# ESP32P4.net
KiCad netlist of a schematic drawn in Altium Designer
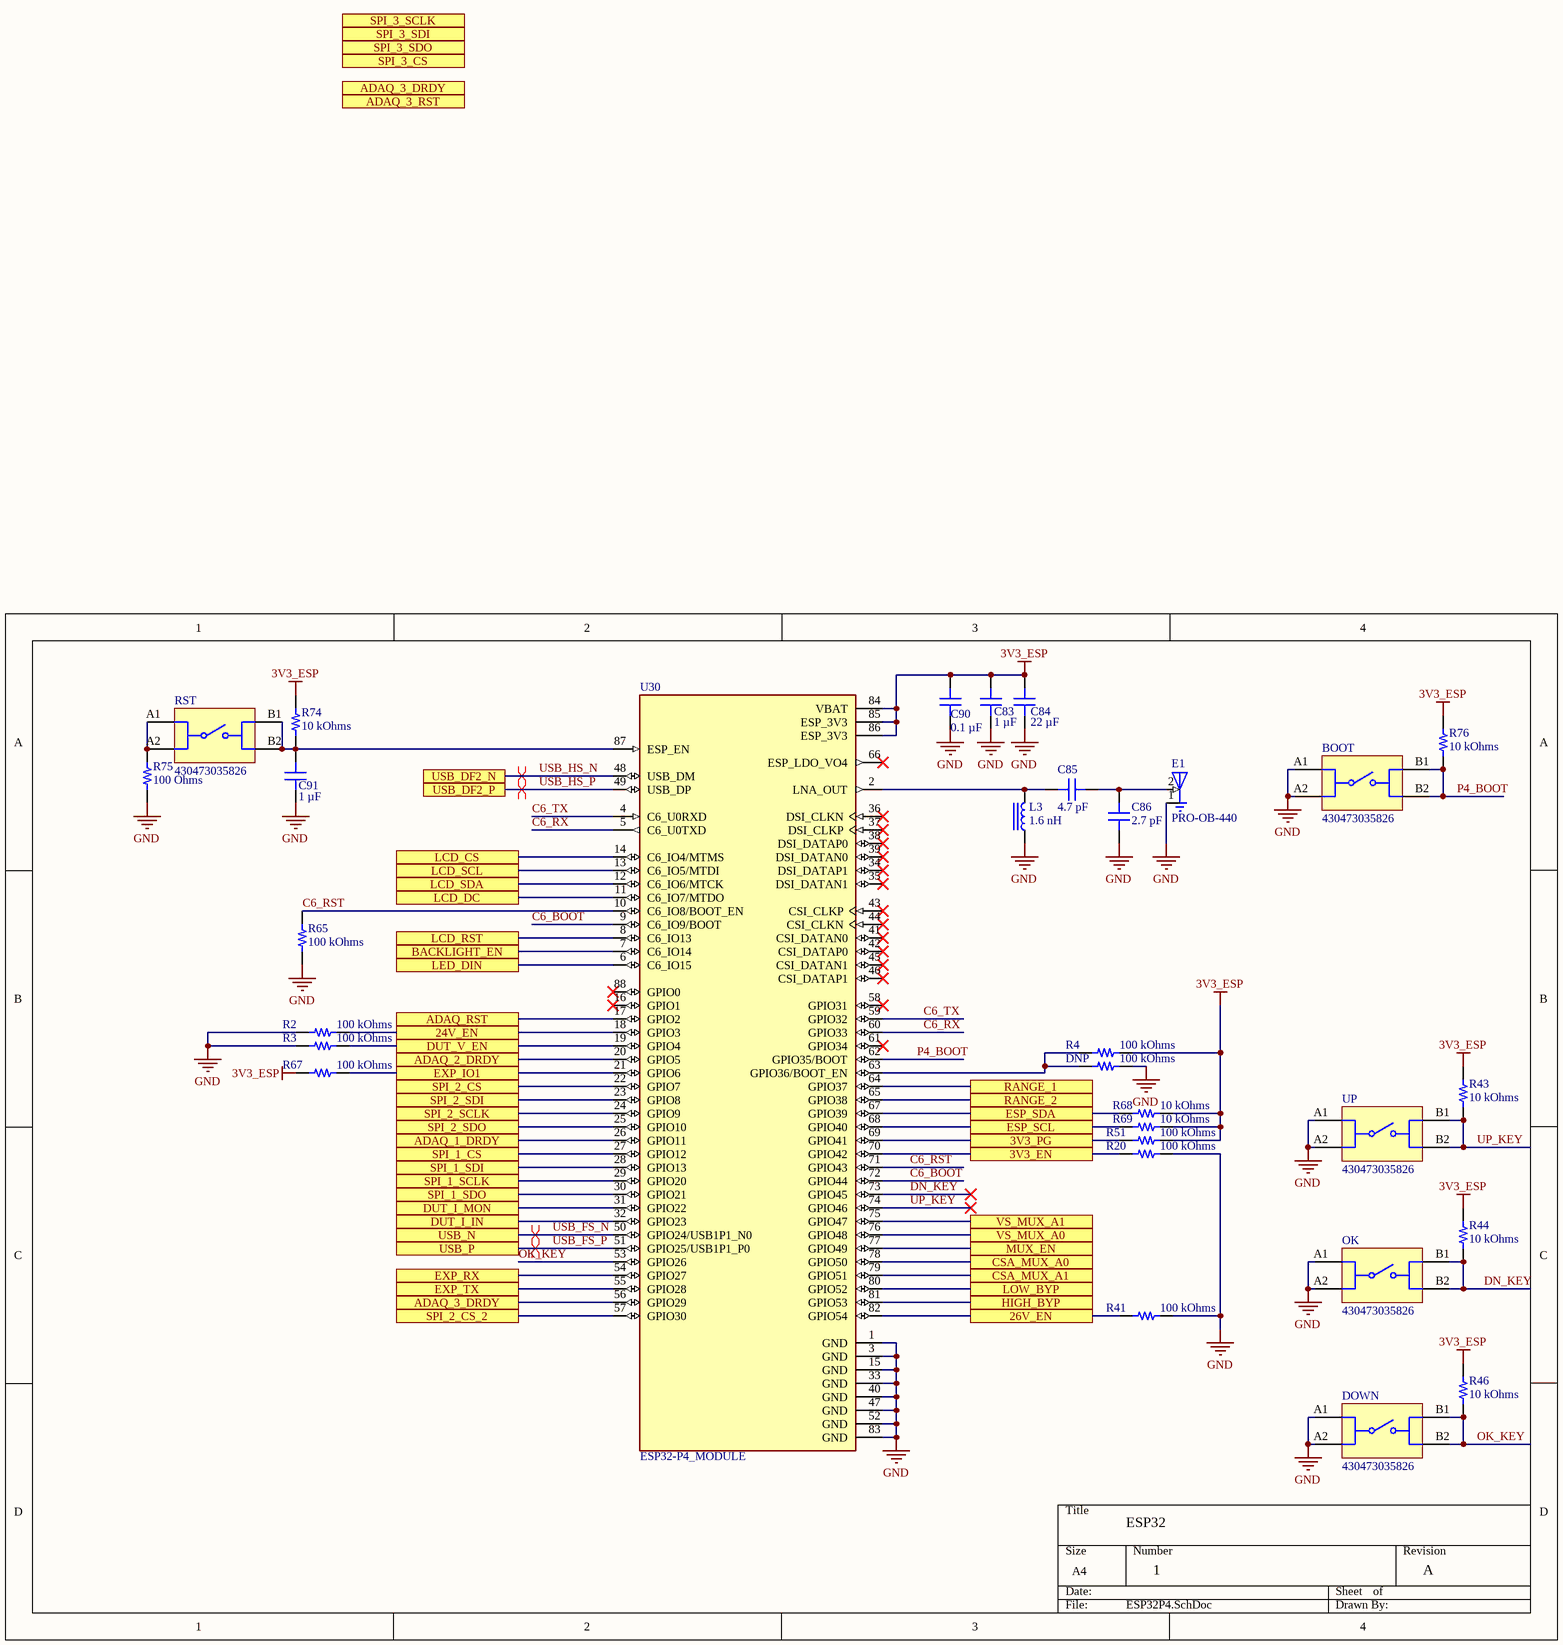
[diagram p0: ESP32P4.SchDoc]

(export (version "E")
  (design (tool "Eeschema 10.0.6"))
  (components
    (comp (ref "BOOT")
      (value "430473035826")
      (footprint "430473035826")
      (description "Switch Tactile Spst-no 0.05A 12V")
      (libsource (lib "Altium Content Vault") (part "SPST-NO_4P"))
    )
    (comp (ref "C83")
      (value "1 µF")
      (footprint "CAP 0603_1608")
      (description "SMT Capacitor")
      (fields
        (field (name "PART NUMBER") "GMC10X7R105M50NT")
        (field (name "MANUFACTURER") "Cal-Chip Electronics, Inc.")
      )
      (libsource (lib "Altium DB") (part "Capacitor"))
    )
    (comp (ref "C84")
      (value "22 µF")
      (footprint "CAP 0603_1608")
      (description "SMT Capacitor")
      (fields
        (field (name "PART NUMBER") "GRM188C61C226ME01D")
        (field (name "MANUFACTURER") "Murata Electronics")
      )
      (libsource (lib "Altium DB") (part "Capacitor"))
    )
    (comp (ref "C85")
      (value "4.7 pF")
      (footprint "CAP 0603_1608")
      (description "SMT Capacitor")
      (fields (field (name "PART NUMBER") "06035C4R7KAT2A") (field (name "MANUFACTURER") "KYOCERA AVX"))
      (libsource (lib "Altium DB") (part "Capacitor"))
    )
    (comp (ref "C86")
      (value "2.7 pF")
      (footprint "CAP 0603_1608")
      (description "SMT Capacitor")
      (fields (field (name "PART NUMBER") "C0603C279D5GAC7867") (field (name "MANUFACTURER") "KEMET"))
      (libsource (lib "Altium DB") (part "Capacitor"))
    )
    (comp (ref "C90")
      (value "0.1 µF")
      (footprint "CAP 0603_1608")
      (description "SMT Capacitor")
      (fields (field (name "PART NUMBER") "C0603C104M5RACTU") (field (name "MANUFACTURER") "KEMET"))
      (libsource (lib "Altium DB") (part "Capacitor"))
    )
    (comp (ref "C91")
      (value "1 µF")
      (footprint "CAP 0603_1608")
      (description "SMT Capacitor")
      (fields
        (field (name "PART NUMBER") "GMC10X7R105M50NT")
        (field (name "MANUFACTURER") "Cal-Chip Electronics, Inc.")
      )
      (libsource (lib "Altium DB") (part "Capacitor"))
    )
    (comp (ref "DNP")
      (value "100 kOhms")
      (footprint "RES 0603_1608")
      (description "RES SMD 100K OHM 1% 1/3W 0603")
      (fields
        (field (name "MANUFACTURER") "Panasonic Electronic Components")
        (field (name "PART NUMBER") "ERJ-PA3F1003V")
      )
      (libsource (lib "Altium DB") (part "Resistor"))
    )
    (comp (ref "DOWN")
      (value "430473035826")
      (footprint "430473035826")
      (description "Switch Tactile Spst-no 0.05A 12V")
      (libsource (lib "Altium Content Vault") (part "SPST-NO_4P"))
    )
    (comp (ref "E1")
      (value "PRO-OB-440")
      (footprint "XDCR_PRO-OB-440")
      (fields (field (name "MF") "Abracon"))
      (libsource (lib "Lib") (part "PRO-OB-440"))
    )
    (comp (ref "L3")
      (value "1.6 nH")
      (footprint "Murata LQW18 0603")
      (description "FIXED IND 1.6NH 700MA 30MOHM SMD")
      (fields
        (field (name "PART NUMBER") "LQW18AS1N6J0ZD")
        (field (name "MANUFACTURER") "Murata Electronics")
      )
      (libsource (lib "Altium DB") (part "Inductor"))
    )
    (comp (ref "OK")
      (value "430473035826")
      (footprint "430473035826")
      (description "Switch Tactile Spst-no 0.05A 12V")
      (libsource (lib "Altium Content Vault") (part "SPST-NO_4P"))
    )
    (comp (ref "R2")
      (value "100 kOhms")
      (footprint "RES 0603_1608")
      (description "RES SMD 100K OHM 1% 1/3W 0603")
      (fields
        (field (name "MANUFACTURER") "Panasonic Electronic Components")
        (field (name "PART NUMBER") "ERJ-PA3F1003V")
      )
      (libsource (lib "Altium DB") (part "Resistor"))
    )
    (comp (ref "R3")
      (value "100 kOhms")
      (footprint "RES 0603_1608")
      (description "RES SMD 100K OHM 1% 1/3W 0603")
      (fields
        (field (name "MANUFACTURER") "Panasonic Electronic Components")
        (field (name "PART NUMBER") "ERJ-PA3F1003V")
      )
      (libsource (lib "Altium DB") (part "Resistor"))
    )
    (comp (ref "R4")
      (value "100 kOhms")
      (footprint "RES 0603_1608")
      (description "RES SMD 100K OHM 1% 1/3W 0603")
      (fields
        (field (name "MANUFACTURER") "Panasonic Electronic Components")
        (field (name "PART NUMBER") "ERJ-PA3F1003V")
      )
      (libsource (lib "Altium DB") (part "Resistor"))
    )
    (comp (ref "R20")
      (value "100 kOhms")
      (footprint "RES 0603_1608")
      (description "RES SMD 100K OHM 1% 1/3W 0603")
      (fields
        (field (name "MANUFACTURER") "Panasonic Electronic Components")
        (field (name "PART NUMBER") "ERJ-PA3F1003V")
      )
      (libsource (lib "Altium DB") (part "Resistor"))
    )
    (comp (ref "R41")
      (value "100 kOhms")
      (footprint "RES 0603_1608")
      (description "RES SMD 100K OHM 1% 1/3W 0603")
      (fields
        (field (name "MANUFACTURER") "Panasonic Electronic Components")
        (field (name "PART NUMBER") "ERJ-PA3F1003V")
      )
      (libsource (lib "Altium DB") (part "Resistor"))
    )
    (comp (ref "R43")
      (value "10 kOhms")
      (footprint "RES 0603_1608")
      (description "RES SMD 10K OHM 1% 1/3W 0603")
      (fields
        (field (name "MANUFACTURER") "Panasonic Electronic Components")
        (field (name "PART NUMBER") "ERJ-PA3F1002V")
      )
      (libsource (lib "Altium DB") (part "Resistor"))
    )
    (comp (ref "R44")
      (value "10 kOhms")
      (footprint "RES 0603_1608")
      (description "RES SMD 10K OHM 1% 1/3W 0603")
      (fields
        (field (name "MANUFACTURER") "Panasonic Electronic Components")
        (field (name "PART NUMBER") "ERJ-PA3F1002V")
      )
      (libsource (lib "Altium DB") (part "Resistor"))
    )
    (comp (ref "R46")
      (value "10 kOhms")
      (footprint "RES 0603_1608")
      (description "RES SMD 10K OHM 1% 1/3W 0603")
      (fields
        (field (name "MANUFACTURER") "Panasonic Electronic Components")
        (field (name "PART NUMBER") "ERJ-PA3F1002V")
      )
      (libsource (lib "Altium DB") (part "Resistor"))
    )
    (comp (ref "R51")
      (value "100 kOhms")
      (footprint "RES 0603_1608")
      (description "RES SMD 100K OHM 1% 1/3W 0603")
      (fields
        (field (name "MANUFACTURER") "Panasonic Electronic Components")
        (field (name "PART NUMBER") "ERJ-PA3F1003V")
      )
      (libsource (lib "Altium DB") (part "Resistor"))
    )
    (comp (ref "R65")
      (value "100 kOhms")
      (footprint "RES 0603_1608")
      (description "RES SMD 100K OHM 1% 1/3W 0603")
      (fields
        (field (name "MANUFACTURER") "Panasonic Electronic Components")
        (field (name "PART NUMBER") "ERJ-PA3F1003V")
      )
      (libsource (lib "Altium DB") (part "Resistor"))
    )
    (comp (ref "R67")
      (value "100 kOhms")
      (footprint "RES 0603_1608")
      (description "RES SMD 100K OHM 1% 1/3W 0603")
      (fields
        (field (name "MANUFACTURER") "Panasonic Electronic Components")
        (field (name "PART NUMBER") "ERJ-PA3F1003V")
      )
      (libsource (lib "Altium DB") (part "Resistor"))
    )
    (comp (ref "R68")
      (value "10 kOhms")
      (footprint "RES 0603_1608")
      (description "RES SMD 10K OHM 1% 1/3W 0603")
      (fields
        (field (name "MANUFACTURER") "Panasonic Electronic Components")
        (field (name "PART NUMBER") "ERJ-PA3F1002V")
      )
      (libsource (lib "Altium DB") (part "Resistor"))
    )
    (comp (ref "R69")
      (value "10 kOhms")
      (footprint "RES 0603_1608")
      (description "RES SMD 10K OHM 1% 1/3W 0603")
      (fields
        (field (name "MANUFACTURER") "Panasonic Electronic Components")
        (field (name "PART NUMBER") "ERJ-PA3F1002V")
      )
      (libsource (lib "Altium DB") (part "Resistor"))
    )
    (comp (ref "R74")
      (value "10 kOhms")
      (footprint "RES 0603_1608")
      (description "RES SMD 10K OHM 1% 1/3W 0603")
      (fields
        (field (name "MANUFACTURER") "Panasonic Electronic Components")
        (field (name "PART NUMBER") "ERJ-PA3F1002V")
      )
      (libsource (lib "Altium DB") (part "Resistor"))
    )
    (comp (ref "R75")
      (value "100 Ohms")
      (footprint "RES 0603_1608")
      (description "RES SMD 100 OHM 1% 1/3W 0603")
      (fields
        (field (name "MANUFACTURER") "Panasonic Electronic Components")
        (field (name "PART NUMBER") "ERJ-PA3F1000V")
      )
      (libsource (lib "") (part "Resistor_1"))
    )
    (comp (ref "R76")
      (value "10 kOhms")
      (footprint "RES 0603_1608")
      (description "RES SMD 10K OHM 1% 1/3W 0603")
      (fields
        (field (name "MANUFACTURER") "Panasonic Electronic Components")
        (field (name "PART NUMBER") "ERJ-PA3F1002V")
      )
      (libsource (lib "Altium DB") (part "Resistor"))
    )
    (comp (ref "RST")
      (value "430473035826")
      (footprint "430473035826")
      (description "Switch Tactile Spst-no 0.05A 12V")
      (libsource (lib "Altium Content Vault") (part "SPST-NO_4P"))
    )
    (comp (ref "U30")
      (value "ESP32-P4_MODULE")
      (footprint "XCVR_ESP32-P4_MODULE")
      (description "Dual-core RISC-V high-performance module")
      (fields (field (name "MF") "Waveshare Electronics") (field (name "MP") "ESP32-P4 Module"))
      (libsource (lib "Lib") (part "ESP32-P4_MODULE"))
    )
    (comp (ref "UP")
      (value "430473035826")
      (footprint "430473035826")
      (description "Switch Tactile Spst-no 0.05A 12V")
      (libsource (lib "Altium Content Vault") (part "SPST-NO_4P"))
    )
  )
  (nets
    (net (code "1") (name "/3V3_EN") (class "Default")
      (node (ref "R20") (pin "1") (pinfunction "1_1") (pintype "passive"))
      (node (ref "U30") (pin "70") (pinfunction "GPIO42_70") (pintype "bidirectional"))
    )
    (net (code "2") (name "/3V3_PG") (class "Default")
      (node (ref "R51") (pin "1") (pinfunction "1_1") (pintype "passive"))
      (node (ref "U30") (pin "69") (pinfunction "GPIO41_69") (pintype "bidirectional"))
    )
    (net (code "3") (name "/24V_EN") (class "Default")
      (node (ref "R2") (pin "2") (pinfunction "2_2") (pintype "passive"))
      (node (ref "U30") (pin "18") (pinfunction "GPIO3_18") (pintype "bidirectional"))
    )
    (net (code "4") (name "/26V_EN") (class "Default")
      (node (ref "R41") (pin "1") (pinfunction "1_1") (pintype "passive"))
      (node (ref "U30") (pin "82") (pinfunction "GPIO54_82") (pintype "bidirectional"))
    )
    (net (code "5") (name "/ADAQ_1_DRDY") (class "Default")
      (node (ref "U30") (pin "26") (pinfunction "GPIO11_26") (pintype "bidirectional"))
    )
    (net (code "6") (name "/ADAQ_2_DRDY") (class "Default")
      (node (ref "U30") (pin "20") (pinfunction "GPIO5_20") (pintype "bidirectional"))
    )
    (net (code "7") (name "/ADAQ_3_DRDY") (class "Default")
      (node (ref "U30") (pin "56") (pinfunction "GPIO29_56") (pintype "bidirectional"))
    )
    (net (code "9") (name "/ADAQ_RST") (class "Default")
      (node (ref "U30") (pin "17") (pinfunction "GPIO2_17") (pintype "bidirectional"))
    )
    (net (code "10") (name "/BACKLIGHT_EN") (class "Default")
      (node (ref "U30") (pin "7") (pinfunction "C6_IO14_7") (pintype "bidirectional"))
    )
    (net (code "11") (name "/C6_BOOT") (class "Default")
      (node (ref "U30") (pin "72") (pinfunction "GPIO44_72") (pintype "bidirectional"))
      (node (ref "U30") (pin "9") (pinfunction "C6_IO9/BOOT_9") (pintype "bidirectional"))
    )
    (net (code "12") (name "/C6_RST") (class "Default")
      (node (ref "R65") (pin "1") (pinfunction "1_1") (pintype "passive"))
      (node (ref "U30") (pin "10") (pinfunction "C6_IO8/BOOT_EN_10") (pintype "bidirectional"))
      (node (ref "U30") (pin "71") (pinfunction "GPIO43_71") (pintype "bidirectional"))
    )
    (net (code "13") (name "/C6_RX") (class "Default")
      (node (ref "U30") (pin "5") (pinfunction "C6_U0TXD_5") (pintype "output"))
      (node (ref "U30") (pin "60") (pinfunction "GPIO33_60") (pintype "bidirectional"))
    )
    (net (code "14") (name "/C6_TX") (class "Default")
      (node (ref "U30") (pin "4") (pinfunction "C6_U0RXD_4") (pintype "input"))
      (node (ref "U30") (pin "59") (pinfunction "GPIO32_59") (pintype "bidirectional"))
    )
    (net (code "15") (name "/CSA_MUX_A0") (class "Default")
      (node (ref "U30") (pin "78") (pinfunction "GPIO50_78") (pintype "bidirectional"))
    )
    (net (code "16") (name "/CSA_MUX_A1") (class "Default")
      (node (ref "U30") (pin "79") (pinfunction "GPIO51_79") (pintype "bidirectional"))
    )
    (net (code "17") (name "/DN_KEY") (class "Default")
      (node (ref "OK") (pin "B1") (pinfunction "B1_B1") (pintype "passive"))
      (node (ref "OK") (pin "B2") (pinfunction "B2_B2") (pintype "passive"))
      (node (ref "R44") (pin "1") (pinfunction "1_1") (pintype "passive"))
      (node (ref "U30") (pin "73") (pinfunction "GPIO45_73") (pintype "bidirectional"))
    )
    (net (code "18") (name "/DUT_I_IN") (class "Default")
      (node (ref "U30") (pin "32") (pinfunction "GPIO23_32") (pintype "bidirectional"))
    )
    (net (code "19") (name "/DUT_I_MON") (class "Default")
      (node (ref "U30") (pin "31") (pinfunction "GPIO22_31") (pintype "bidirectional"))
    )
    (net (code "20") (name "/DUT_V_EN") (class "Default")
      (node (ref "R3") (pin "2") (pinfunction "2_2") (pintype "passive"))
      (node (ref "U30") (pin "19") (pinfunction "GPIO4_19") (pintype "bidirectional"))
    )
    (net (code "21") (name "/ESP_SCL") (class "Default")
      (node (ref "R69") (pin "1") (pinfunction "1_1") (pintype "passive"))
      (node (ref "U30") (pin "68") (pinfunction "GPIO40_68") (pintype "bidirectional"))
    )
    (net (code "22") (name "/ESP_SDA") (class "Default")
      (node (ref "R68") (pin "1") (pinfunction "1_1") (pintype "passive"))
      (node (ref "U30") (pin "67") (pinfunction "GPIO39_67") (pintype "bidirectional"))
    )
    (net (code "23") (name "/EXP_IO1") (class "Default")
      (node (ref "R67") (pin "2") (pinfunction "2_2") (pintype "passive"))
      (node (ref "U30") (pin "21") (pinfunction "GPIO6_21") (pintype "bidirectional"))
    )
    (net (code "24") (name "/EXP_RX") (class "Default")
      (node (ref "U30") (pin "54") (pinfunction "GPIO27_54") (pintype "bidirectional"))
    )
    (net (code "25") (name "/EXP_TX") (class "Default")
      (node (ref "U30") (pin "55") (pinfunction "GPIO28_55") (pintype "bidirectional"))
    )
    (net (code "26") (name "/HIGH_BYP") (class "Default")
      (node (ref "U30") (pin "81") (pinfunction "GPIO53_81") (pintype "bidirectional"))
    )
    (net (code "27") (name "/LCD_CS") (class "Default")
      (node (ref "U30") (pin "14") (pinfunction "C6_IO4/MTMS_14") (pintype "bidirectional"))
    )
    (net (code "28") (name "/LCD_DC") (class "Default")
      (node (ref "U30") (pin "11") (pinfunction "C6_IO7/MTDO_11") (pintype "bidirectional"))
    )
    (net (code "29") (name "/LCD_RST") (class "Default")
      (node (ref "U30") (pin "8") (pinfunction "C6_IO13_8") (pintype "bidirectional"))
    )
    (net (code "30") (name "/LCD_SCL") (class "Default")
      (node (ref "U30") (pin "13") (pinfunction "C6_IO5/MTDI_13") (pintype "bidirectional"))
    )
    (net (code "31") (name "/LCD_SDA") (class "Default")
      (node (ref "U30") (pin "12") (pinfunction "C6_IO6/MTCK_12") (pintype "bidirectional"))
    )
    (net (code "32") (name "/LED_DIN") (class "Default")
      (node (ref "U30") (pin "6") (pinfunction "C6_IO15_6") (pintype "bidirectional"))
    )
    (net (code "33") (name "/LOW_BYP") (class "Default")
      (node (ref "U30") (pin "80") (pinfunction "GPIO52_80") (pintype "bidirectional"))
    )
    (net (code "34") (name "/MUX_EN") (class "Default")
      (node (ref "U30") (pin "77") (pinfunction "GPIO49_77") (pintype "bidirectional"))
    )
    (net (code "35") (name "/OK_KEY") (class "Default")
      (node (ref "DOWN") (pin "B1") (pinfunction "B1_B1") (pintype "passive"))
      (node (ref "DOWN") (pin "B2") (pinfunction "B2_B2") (pintype "passive"))
      (node (ref "R46") (pin "1") (pinfunction "1_1") (pintype "passive"))
      (node (ref "U30") (pin "53") (pinfunction "GPIO26_53") (pintype "bidirectional"))
    )
    (net (code "36") (name "/P4_BOOT") (class "Default")
      (node (ref "BOOT") (pin "B1") (pinfunction "B1_B1") (pintype "passive"))
      (node (ref "BOOT") (pin "B2") (pinfunction "B2_B2") (pintype "passive"))
      (node (ref "R76") (pin "1") (pinfunction "1_1") (pintype "passive"))
      (node (ref "U30") (pin "62") (pinfunction "GPIO35/BOOT_62") (pintype "bidirectional"))
    )
    (net (code "37") (name "/RANGE_1") (class "Default")
      (node (ref "U30") (pin "64") (pinfunction "GPIO37_64") (pintype "bidirectional"))
    )
    (net (code "38") (name "/RANGE_2") (class "Default")
      (node (ref "U30") (pin "65") (pinfunction "GPIO38_65") (pintype "bidirectional"))
    )
    (net (code "39") (name "/SPI_1_CS") (class "Default")
      (node (ref "U30") (pin "27") (pinfunction "GPIO12_27") (pintype "bidirectional"))
    )
    (net (code "40") (name "/SPI_1_SCLK") (class "Default")
      (node (ref "U30") (pin "29") (pinfunction "GPIO20_29") (pintype "bidirectional"))
    )
    (net (code "41") (name "/SPI_1_SDI") (class "Default")
      (node (ref "U30") (pin "28") (pinfunction "GPIO13_28") (pintype "bidirectional"))
    )
    (net (code "42") (name "/SPI_1_SDO") (class "Default")
      (node (ref "U30") (pin "30") (pinfunction "GPIO21_30") (pintype "bidirectional"))
    )
    (net (code "43") (name "/SPI_2_CS") (class "Default")
      (node (ref "U30") (pin "22") (pinfunction "GPIO7_22") (pintype "bidirectional"))
    )
    (net (code "44") (name "/SPI_2_CS_2") (class "Default")
      (node (ref "U30") (pin "57") (pinfunction "GPIO30_57") (pintype "bidirectional"))
    )
    (net (code "45") (name "/SPI_2_SCLK") (class "Default")
      (node (ref "U30") (pin "24") (pinfunction "GPIO9_24") (pintype "bidirectional"))
    )
    (net (code "46") (name "/SPI_2_SDI") (class "Default")
      (node (ref "U30") (pin "23") (pinfunction "GPIO8_23") (pintype "bidirectional"))
    )
    (net (code "47") (name "/SPI_2_SDO") (class "Default")
      (node (ref "U30") (pin "25") (pinfunction "GPIO10_25") (pintype "bidirectional"))
    )
    (net (code "52") (name "/UP_KEY") (class "Default")
      (node (ref "R43") (pin "1") (pinfunction "1_1") (pintype "passive"))
      (node (ref "U30") (pin "74") (pinfunction "GPIO46_74") (pintype "bidirectional"))
      (node (ref "UP") (pin "B1") (pinfunction "B1_B1") (pintype "passive"))
      (node (ref "UP") (pin "B2") (pinfunction "B2_B2") (pintype "passive"))
    )
    (net (code "53") (name "/USB_FS_N") (class "Default")
      (node (ref "U30") (pin "50") (pinfunction "GPIO24/USB1P1_N0_50") (pintype "bidirectional"))
    )
    (net (code "54") (name "/USB_FS_P") (class "Default")
      (node (ref "U30") (pin "51") (pinfunction "GPIO25/USB1P1_P0_51") (pintype "bidirectional"))
    )
    (net (code "55") (name "/USB_HS_N") (class "Default")
      (node (ref "U30") (pin "48") (pinfunction "USB_DM_48") (pintype "bidirectional"))
    )
    (net (code "56") (name "/USB_HS_P") (class "Default")
      (node (ref "U30") (pin "49") (pinfunction "USB_DP_49") (pintype "bidirectional"))
    )
    (net (code "57") (name "/VS_MUX_A0") (class "Default")
      (node (ref "U30") (pin "76") (pinfunction "GPIO48_76") (pintype "bidirectional"))
    )
    (net (code "58") (name "/VS_MUX_A1") (class "Default")
      (node (ref "U30") (pin "75") (pinfunction "GPIO47_75") (pintype "bidirectional"))
    )
    (net (code "59") (name "3V3_ESP") (class "Default")
      (node (ref "C83") (pin "2") (pinfunction "2_2") (pintype "passive"))
      (node (ref "C84") (pin "2") (pinfunction "2_2") (pintype "passive"))
      (node (ref "C90") (pin "2") (pinfunction "2_2") (pintype "passive"))
      (node (ref "R4") (pin "2") (pinfunction "2_2") (pintype "passive"))
      (node (ref "R43") (pin "2") (pinfunction "2_2") (pintype "passive"))
      (node (ref "R44") (pin "2") (pinfunction "2_2") (pintype "passive"))
      (node (ref "R46") (pin "2") (pinfunction "2_2") (pintype "passive"))
      (node (ref "R51") (pin "2") (pinfunction "2_2") (pintype "passive"))
      (node (ref "R67") (pin "1") (pinfunction "1_1") (pintype "passive"))
      (node (ref "R68") (pin "2") (pinfunction "2_2") (pintype "passive"))
      (node (ref "R69") (pin "2") (pinfunction "2_2") (pintype "passive"))
      (node (ref "R74") (pin "2") (pinfunction "2_2") (pintype "passive"))
      (node (ref "R76") (pin "2") (pinfunction "2_2") (pintype "passive"))
      (node (ref "U30") (pin "84") (pinfunction "VBAT_84") (pintype "power_in"))
      (node (ref "U30") (pin "85") (pinfunction "ESP_3V3_85") (pintype "power_in"))
      (node (ref "U30") (pin "86") (pinfunction "ESP_3V3_86") (pintype "power_in"))
    )
    (net (code "60") (name "GND") (class "Default")
      (node (ref "BOOT") (pin "A1") (pinfunction "A1_A1") (pintype "passive"))
      (node (ref "BOOT") (pin "A2") (pinfunction "A2_A2") (pintype "passive"))
      (node (ref "C83") (pin "1") (pinfunction "1_1") (pintype "passive"))
      (node (ref "C84") (pin "1") (pinfunction "1_1") (pintype "passive"))
      (node (ref "C86") (pin "1") (pinfunction "1_1") (pintype "passive"))
      (node (ref "C90") (pin "1") (pinfunction "1_1") (pintype "passive"))
      (node (ref "C91") (pin "1") (pinfunction "1_1") (pintype "passive"))
      (node (ref "DNP") (pin "2") (pinfunction "2_2") (pintype "passive"))
      (node (ref "DOWN") (pin "A1") (pinfunction "A1_A1") (pintype "passive"))
      (node (ref "DOWN") (pin "A2") (pinfunction "A2_A2") (pintype "passive"))
      (node (ref "E1") (pin "1") (pinfunction "GND_1") (pintype "power_in"))
      (node (ref "L3") (pin "1") (pinfunction "1_1") (pintype "passive"))
      (node (ref "OK") (pin "A1") (pinfunction "A1_A1") (pintype "passive"))
      (node (ref "OK") (pin "A2") (pinfunction "A2_A2") (pintype "passive"))
      (node (ref "R2") (pin "1") (pinfunction "1_1") (pintype "passive"))
      (node (ref "R20") (pin "2") (pinfunction "2_2") (pintype "passive"))
      (node (ref "R3") (pin "1") (pinfunction "1_1") (pintype "passive"))
      (node (ref "R41") (pin "2") (pinfunction "2_2") (pintype "passive"))
      (node (ref "R65") (pin "2") (pinfunction "2_2") (pintype "passive"))
      (node (ref "R75") (pin "1") (pinfunction "1_1") (pintype "passive"))
      (node (ref "U30") (pin "1") (pinfunction "GND_1") (pintype "power_in"))
      (node (ref "U30") (pin "15") (pinfunction "GND_15") (pintype "power_in"))
      (node (ref "U30") (pin "3") (pinfunction "GND_3") (pintype "power_in"))
      (node (ref "U30") (pin "33") (pinfunction "GND_33") (pintype "power_in"))
      (node (ref "U30") (pin "40") (pinfunction "GND_40") (pintype "power_in"))
      (node (ref "U30") (pin "47") (pinfunction "GND_47") (pintype "power_in"))
      (node (ref "U30") (pin "52") (pinfunction "GND_52") (pintype "power_in"))
      (node (ref "U30") (pin "83") (pinfunction "GND_83") (pintype "power_in"))
      (node (ref "UP") (pin "A1") (pinfunction "A1_A1") (pintype "passive"))
      (node (ref "UP") (pin "A2") (pinfunction "A2_A2") (pintype "passive"))
    )
    (net (code "61") (name "Net-(E1-FEED)") (class "Default")
      (node (ref "C85") (pin "1") (pinfunction "1_1") (pintype "passive"))
      (node (ref "C86") (pin "2") (pinfunction "2_2") (pintype "passive"))
      (node (ref "E1") (pin "2") (pinfunction "FEED_2") (pintype "input"))
    )
    (net (code "62") (name "Net-(R75-Pad2)") (class "Default")
      (node (ref "R75") (pin "2") (pinfunction "2_2") (pintype "passive"))
      (node (ref "RST") (pin "A1") (pinfunction "A1_A1") (pintype "passive"))
      (node (ref "RST") (pin "A2") (pinfunction "A2_A2") (pintype "passive"))
    )
    (net (code "63") (name "Net-(U30-ESP_EN)") (class "Default")
      (node (ref "C91") (pin "2") (pinfunction "2_2") (pintype "passive"))
      (node (ref "R74") (pin "1") (pinfunction "1_1") (pintype "passive"))
      (node (ref "RST") (pin "B1") (pinfunction "B1_B1") (pintype "passive"))
      (node (ref "RST") (pin "B2") (pinfunction "B2_B2") (pintype "passive"))
      (node (ref "U30") (pin "87") (pinfunction "ESP_EN_87") (pintype "input"))
    )
    (net (code "64") (name "Net-(U30-GPIO36{slash}BOOT_EN)") (class "Default")
      (node (ref "DNP") (pin "1") (pinfunction "1_1") (pintype "passive"))
      (node (ref "R4") (pin "1") (pinfunction "1_1") (pintype "passive"))
      (node (ref "U30") (pin "63") (pinfunction "GPIO36/BOOT_EN_63") (pintype "bidirectional"))
    )
    (net (code "65") (name "Net-(U30-LNA_OUT)") (class "Default")
      (node (ref "C85") (pin "2") (pinfunction "2_2") (pintype "passive"))
      (node (ref "L3") (pin "2") (pinfunction "2_2") (pintype "passive"))
      (node (ref "U30") (pin "2") (pinfunction "LNA_OUT_2") (pintype "output"))
    )
    (net (code "66") (name "unconnected-(U30-CSI_CLKN-Pad44)") (class "Default")
      (node (ref "U30") (pin "44") (pinfunction "CSI_CLKN_44") (pintype "input+no_connect"))
    )
    (net (code "67") (name "unconnected-(U30-CSI_CLKP-Pad43)") (class "Default")
      (node (ref "U30") (pin "43") (pinfunction "CSI_CLKP_43") (pintype "input+no_connect"))
    )
    (net (code "68") (name "unconnected-(U30-CSI_DATAN0-Pad41)") (class "Default")
      (node (ref "U30") (pin "41") (pinfunction "CSI_DATAN0_41") (pintype "bidirectional+no_connect"))
    )
    (net (code "69") (name "unconnected-(U30-CSI_DATAN1-Pad45)") (class "Default")
      (node (ref "U30") (pin "45") (pinfunction "CSI_DATAN1_45") (pintype "bidirectional+no_connect"))
    )
    (net (code "70") (name "unconnected-(U30-CSI_DATAP0-Pad42)") (class "Default")
      (node (ref "U30") (pin "42") (pinfunction "CSI_DATAP0_42") (pintype "bidirectional+no_connect"))
    )
    (net (code "71") (name "unconnected-(U30-CSI_DATAP1-Pad46)") (class "Default")
      (node (ref "U30") (pin "46") (pinfunction "CSI_DATAP1_46") (pintype "bidirectional+no_connect"))
    )
    (net (code "72") (name "unconnected-(U30-DSI_CLKN-Pad36)") (class "Default")
      (node (ref "U30") (pin "36") (pinfunction "DSI_CLKN_36") (pintype "input+no_connect"))
    )
    (net (code "73") (name "unconnected-(U30-DSI_CLKP-Pad37)") (class "Default")
      (node (ref "U30") (pin "37") (pinfunction "DSI_CLKP_37") (pintype "input+no_connect"))
    )
    (net (code "74") (name "unconnected-(U30-DSI_DATAN0-Pad39)") (class "Default")
      (node (ref "U30") (pin "39") (pinfunction "DSI_DATAN0_39") (pintype "bidirectional+no_connect"))
    )
    (net (code "75") (name "unconnected-(U30-DSI_DATAN1-Pad35)") (class "Default")
      (node (ref "U30") (pin "35") (pinfunction "DSI_DATAN1_35") (pintype "bidirectional+no_connect"))
    )
    (net (code "76") (name "unconnected-(U30-DSI_DATAP0-Pad38)") (class "Default")
      (node (ref "U30") (pin "38") (pinfunction "DSI_DATAP0_38") (pintype "bidirectional+no_connect"))
    )
    (net (code "77") (name "unconnected-(U30-DSI_DATAP1-Pad34)") (class "Default")
      (node (ref "U30") (pin "34") (pinfunction "DSI_DATAP1_34") (pintype "bidirectional+no_connect"))
    )
    (net (code "78") (name "unconnected-(U30-ESP_LDO_VO4-Pad66)") (class "Default")
      (node (ref "U30") (pin "66") (pinfunction "ESP_LDO_VO4_66") (pintype "output+no_connect"))
    )
    (net (code "79") (name "unconnected-(U30-GPIO0-Pad88)") (class "Default")
      (node (ref "U30") (pin "88") (pinfunction "GPIO0_88") (pintype "bidirectional+no_connect"))
    )
    (net (code "80") (name "unconnected-(U30-GPIO1-Pad16)") (class "Default")
      (node (ref "U30") (pin "16") (pinfunction "GPIO1_16") (pintype "bidirectional+no_connect"))
    )
    (net (code "81") (name "unconnected-(U30-GPIO31-Pad58)") (class "Default")
      (node (ref "U30") (pin "58") (pinfunction "GPIO31_58") (pintype "bidirectional+no_connect"))
    )
    (net (code "82") (name "unconnected-(U30-GPIO34-Pad61)") (class "Default")
      (node (ref "U30") (pin "61") (pinfunction "GPIO34_61") (pintype "bidirectional+no_connect"))
    )
  )
)
